# My_Spot_User_Interface.net
KiCad netlist of a schematic drawn in EasyEDA
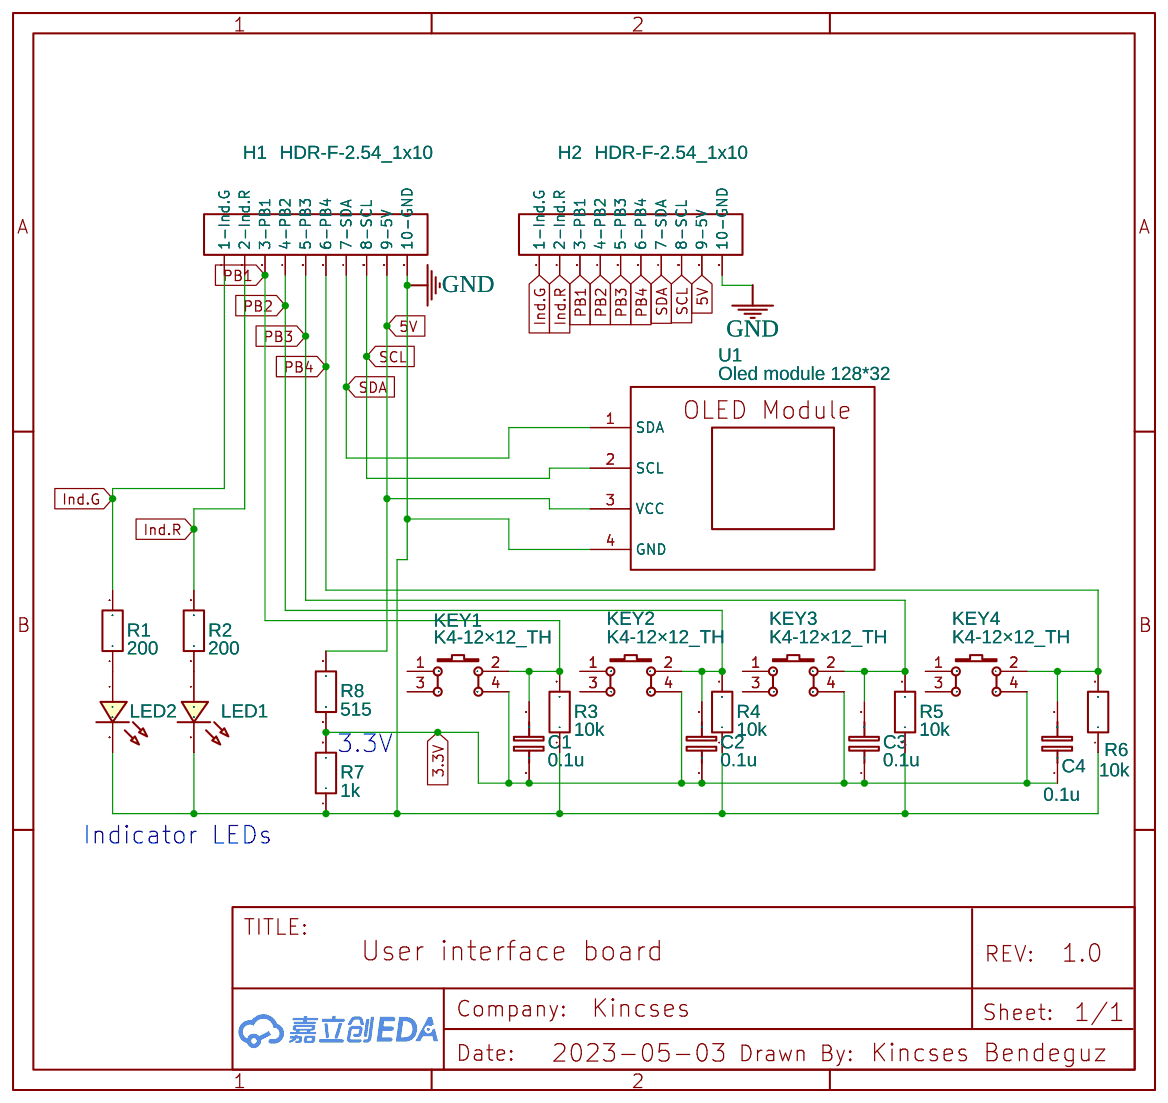
[diagram p0: schematic sheet]

(export (version "E")
  (design (tool "Eeschema 10.0.6"))
  (components
    (comp (ref "C1") (value "0.1u") (libsource (lib "") (part "C_RAD-0.1_EU")))
    (comp (ref "C2") (value "0.1u") (libsource (lib "") (part "C_RAD-0.1_EU")))
    (comp (ref "C3") (value "0.1u") (libsource (lib "") (part "C_RAD-0.1_EU")))
    (comp (ref "C4") (value "0.1u") (libsource (lib "") (part "C_RAD-0.1_EU_1")))
    (comp (ref "H1") (value "HDR-F-2.54_1x10") (libsource (lib "") (part "HDR-F-2.54_1x10")))
    (comp (ref "H2") (value "HDR-F-2.54_1x10") (libsource (lib "") (part "HDR-F-2.54_1x10")))
    (comp (ref "KEY1")
      (value "K4-12×12_TH")
      (fields (field (name "Manufacturer Part") "K2-1103DP-M4SW-04") (field (name "Manufacturer") "韩国韩荣"))
      (libsource (lib "") (part "K4-12×12_TH"))
    )
    (comp (ref "KEY2")
      (value "K4-12×12_TH")
      (fields (field (name "Manufacturer Part") "K2-1103DP-M4SW-04") (field (name "Manufacturer") "韩国韩荣"))
      (libsource (lib "") (part "K4-12×12_TH"))
    )
    (comp (ref "KEY3")
      (value "K4-12×12_TH")
      (fields (field (name "Manufacturer Part") "K2-1103DP-M4SW-04") (field (name "Manufacturer") "韩国韩荣"))
      (libsource (lib "") (part "K4-12×12_TH"))
    )
    (comp (ref "KEY4")
      (value "K4-12×12_TH")
      (fields (field (name "Manufacturer Part") "K2-1103DP-M4SW-04") (field (name "Manufacturer") "韩国韩荣"))
      (libsource (lib "") (part "K4-12×12_TH"))
    )
    (comp (ref "LED1")
      (value "LED-TH-5mm_R")
      (fields
        (field (name "Manufacturer Part") "333-2SURD/S530-A3")
        (field (name "Manufacturer") "EVERLIGHT(台湾亿光)")
      )
      (libsource (lib "") (part "LED-TH-5mm_R"))
    )
    (comp (ref "LED2")
      (value "LED-TH-5mm_G")
      (fields
        (field (name "Manufacturer Part") "333-2SYGD/S530-E2")
        (field (name "Manufacturer") "EVERLIGHT(台湾亿光)")
      )
      (libsource (lib "") (part "LED-TH-5mm_G"))
    )
    (comp (ref "R1") (value "200") (libsource (lib "") (part "R_AXIAL-0.4_EU")))
    (comp (ref "R2") (value "200") (libsource (lib "") (part "R_AXIAL-0.4_EU")))
    (comp (ref "R3") (value "10k") (libsource (lib "") (part "R_AXIAL-0.4_EU")))
    (comp (ref "R4") (value "10k") (libsource (lib "") (part "R_AXIAL-0.4_EU")))
    (comp (ref "R5") (value "10k") (libsource (lib "") (part "R_AXIAL-0.4_EU")))
    (comp (ref "R6") (value "10k") (libsource (lib "") (part "R_AXIAL-0.4_EU")))
    (comp (ref "R7") (value "1k") (libsource (lib "") (part "R_AXIAL-0.4_EU")))
    (comp (ref "R8") (value "515") (libsource (lib "") (part "R_AXIAL-0.4_EU")))
    (comp (ref "U1") (value "Oled module 128*32") (libsource (lib "") (part "Oled module 128*32")))
  )
  (nets
    (net (code "1") (name "3.3V") (class "Default")
      (node (ref "C1") (pin "1") (pinfunction "1_1") (pintype "unspecified"))
      (node (ref "C2") (pin "1") (pinfunction "1_1") (pintype "unspecified"))
      (node (ref "C3") (pin "1") (pinfunction "1_1") (pintype "unspecified"))
      (node (ref "C4") (pin "1") (pinfunction "1_1") (pintype "unspecified"))
      (node (ref "KEY1") (pin "4") (pinfunction "3_4") (pintype "unspecified"))
      (node (ref "KEY2") (pin "4") (pinfunction "3_4") (pintype "unspecified"))
      (node (ref "KEY3") (pin "4") (pinfunction "3_4") (pintype "unspecified"))
      (node (ref "KEY4") (pin "4") (pinfunction "3_4") (pintype "unspecified"))
      (node (ref "R7") (pin "2") (pinfunction "2_2") (pintype "unspecified"))
      (node (ref "R8") (pin "1") (pinfunction "1_1") (pintype "unspecified"))
    )
    (net (code "2") (name "5V") (class "Default")
      (node (ref "H1") (pin "9") (pinfunction "9-5V_9") (pintype "unspecified"))
      (node (ref "H2") (pin "9") (pinfunction "9-5V_9") (pintype "unspecified"))
      (node (ref "R8") (pin "2") (pinfunction "2_2") (pintype "unspecified"))
      (node (ref "U1") (pin "3") (pinfunction "VCC_3") (pintype "unspecified"))
    )
    (net (code "3") (name "GND") (class "Default")
      (node (ref "H1") (pin "10") (pinfunction "10-GND_10") (pintype "unspecified"))
      (node (ref "H2") (pin "10") (pinfunction "10-GND_10") (pintype "unspecified"))
      (node (ref "LED1") (pin "2") (pinfunction "2_2") (pintype "unspecified"))
      (node (ref "LED2") (pin "2") (pinfunction "2_2") (pintype "unspecified"))
      (node (ref "R3") (pin "1") (pinfunction "1_1") (pintype "unspecified"))
      (node (ref "R4") (pin "1") (pinfunction "1_1") (pintype "unspecified"))
      (node (ref "R5") (pin "1") (pinfunction "1_1") (pintype "unspecified"))
      (node (ref "R6") (pin "1") (pinfunction "1_1") (pintype "unspecified"))
      (node (ref "R7") (pin "1") (pinfunction "1_1") (pintype "unspecified"))
      (node (ref "U1") (pin "4") (pinfunction "GND_4") (pintype "unspecified"))
    )
    (net (code "4") (name "Ind.G") (class "Default")
      (node (ref "H1") (pin "1") (pinfunction "1-Ind.G_1") (pintype "unspecified"))
      (node (ref "H2") (pin "1") (pinfunction "1-Ind.G_1") (pintype "unspecified"))
      (node (ref "R1") (pin "2") (pinfunction "2_2") (pintype "unspecified"))
    )
    (net (code "5") (name "Ind.R") (class "Default")
      (node (ref "H1") (pin "2") (pinfunction "2-Ind.R_2") (pintype "unspecified"))
      (node (ref "H2") (pin "2") (pinfunction "2-Ind.R_2") (pintype "unspecified"))
      (node (ref "R2") (pin "2") (pinfunction "2_2") (pintype "unspecified"))
    )
    (net (code "6") (name "Net-(LED1-Pad1)") (class "Default")
      (node (ref "LED1") (pin "1") (pinfunction "1_1") (pintype "unspecified"))
      (node (ref "R2") (pin "1") (pinfunction "1_1") (pintype "unspecified"))
    )
    (net (code "7") (name "Net-(LED2-Pad1)") (class "Default")
      (node (ref "LED2") (pin "1") (pinfunction "1_1") (pintype "unspecified"))
      (node (ref "R1") (pin "1") (pinfunction "1_1") (pintype "unspecified"))
    )
    (net (code "8") (name "PB1") (class "Default")
      (node (ref "C1") (pin "2") (pinfunction "2_2") (pintype "unspecified"))
      (node (ref "H1") (pin "3") (pinfunction "3-PB1_3") (pintype "unspecified"))
      (node (ref "H2") (pin "3") (pinfunction "3-PB1_3") (pintype "unspecified"))
      (node (ref "KEY1") (pin "2") (pinfunction "4_2") (pintype "unspecified"))
      (node (ref "R3") (pin "2") (pinfunction "2_2") (pintype "unspecified"))
    )
    (net (code "9") (name "PB2") (class "Default")
      (node (ref "C2") (pin "2") (pinfunction "2_2") (pintype "unspecified"))
      (node (ref "H1") (pin "4") (pinfunction "4-PB2_4") (pintype "unspecified"))
      (node (ref "H2") (pin "4") (pinfunction "4-PB2_4") (pintype "unspecified"))
      (node (ref "KEY2") (pin "2") (pinfunction "4_2") (pintype "unspecified"))
      (node (ref "R4") (pin "2") (pinfunction "2_2") (pintype "unspecified"))
    )
    (net (code "10") (name "PB3") (class "Default")
      (node (ref "C3") (pin "2") (pinfunction "2_2") (pintype "unspecified"))
      (node (ref "H1") (pin "5") (pinfunction "5-PB3_5") (pintype "unspecified"))
      (node (ref "H2") (pin "5") (pinfunction "5-PB3_5") (pintype "unspecified"))
      (node (ref "KEY3") (pin "2") (pinfunction "4_2") (pintype "unspecified"))
      (node (ref "R5") (pin "2") (pinfunction "2_2") (pintype "unspecified"))
    )
    (net (code "11") (name "PB4") (class "Default")
      (node (ref "C4") (pin "2") (pinfunction "2_2") (pintype "unspecified"))
      (node (ref "H1") (pin "6") (pinfunction "6-PB4_6") (pintype "unspecified"))
      (node (ref "H2") (pin "6") (pinfunction "6-PB4_6") (pintype "unspecified"))
      (node (ref "KEY4") (pin "2") (pinfunction "4_2") (pintype "unspecified"))
      (node (ref "R6") (pin "2") (pinfunction "2_2") (pintype "unspecified"))
    )
    (net (code "12") (name "SCL") (class "Default")
      (node (ref "H1") (pin "8") (pinfunction "8-SCL_8") (pintype "unspecified"))
      (node (ref "H2") (pin "8") (pinfunction "8-SCL_8") (pintype "unspecified"))
      (node (ref "U1") (pin "2") (pinfunction "SCL_2") (pintype "unspecified"))
    )
    (net (code "13") (name "SDA") (class "Default")
      (node (ref "H1") (pin "7") (pinfunction "7-SDA_7") (pintype "unspecified"))
      (node (ref "H2") (pin "7") (pinfunction "7-SDA_7") (pintype "unspecified"))
      (node (ref "U1") (pin "1") (pinfunction "SDA_1") (pintype "unspecified"))
    )
    (net (code "14") (name "unconnected-(KEY1-1-Pad3)") (class "Default")
      (node (ref "KEY1") (pin "3") (pinfunction "1_3") (pintype "unspecified"))
    )
    (net (code "15") (name "unconnected-(KEY1-2-Pad1)") (class "Default")
      (node (ref "KEY1") (pin "1") (pinfunction "2_1") (pintype "unspecified"))
    )
    (net (code "16") (name "unconnected-(KEY2-1-Pad3)") (class "Default")
      (node (ref "KEY2") (pin "3") (pinfunction "1_3") (pintype "unspecified"))
    )
    (net (code "17") (name "unconnected-(KEY2-2-Pad1)") (class "Default")
      (node (ref "KEY2") (pin "1") (pinfunction "2_1") (pintype "unspecified"))
    )
    (net (code "18") (name "unconnected-(KEY3-1-Pad3)") (class "Default")
      (node (ref "KEY3") (pin "3") (pinfunction "1_3") (pintype "unspecified"))
    )
    (net (code "19") (name "unconnected-(KEY3-2-Pad1)") (class "Default")
      (node (ref "KEY3") (pin "1") (pinfunction "2_1") (pintype "unspecified"))
    )
    (net (code "20") (name "unconnected-(KEY4-1-Pad3)") (class "Default")
      (node (ref "KEY4") (pin "3") (pinfunction "1_3") (pintype "unspecified"))
    )
    (net (code "21") (name "unconnected-(KEY4-2-Pad1)") (class "Default")
      (node (ref "KEY4") (pin "1") (pinfunction "2_1") (pintype "unspecified"))
    )
  )
)
